# MOD-Y_cold_V03.net
KiCad netlist of a schematic drawn in EAGLE
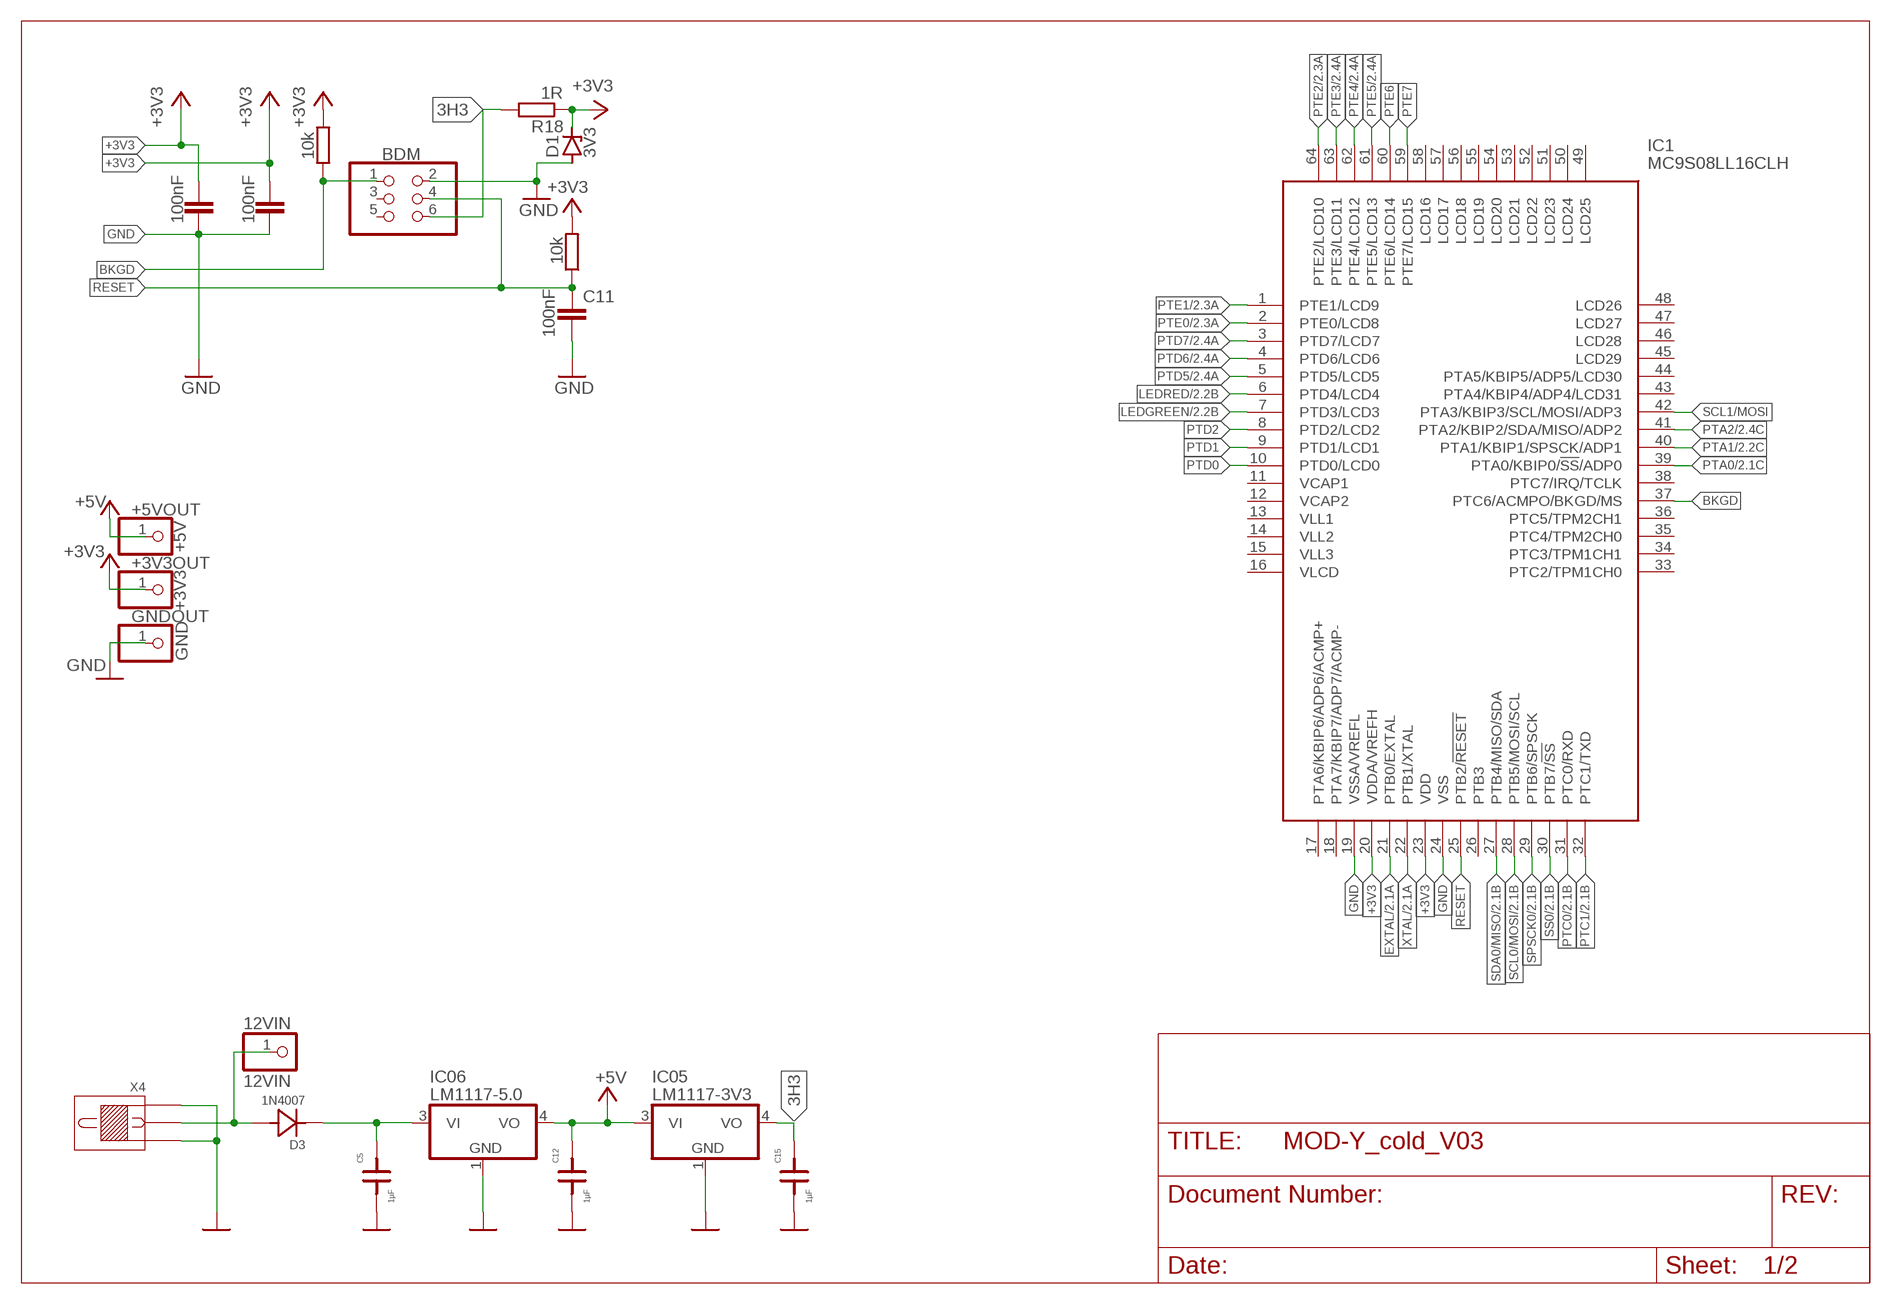
[diagram p0: schematic, sheet 1]
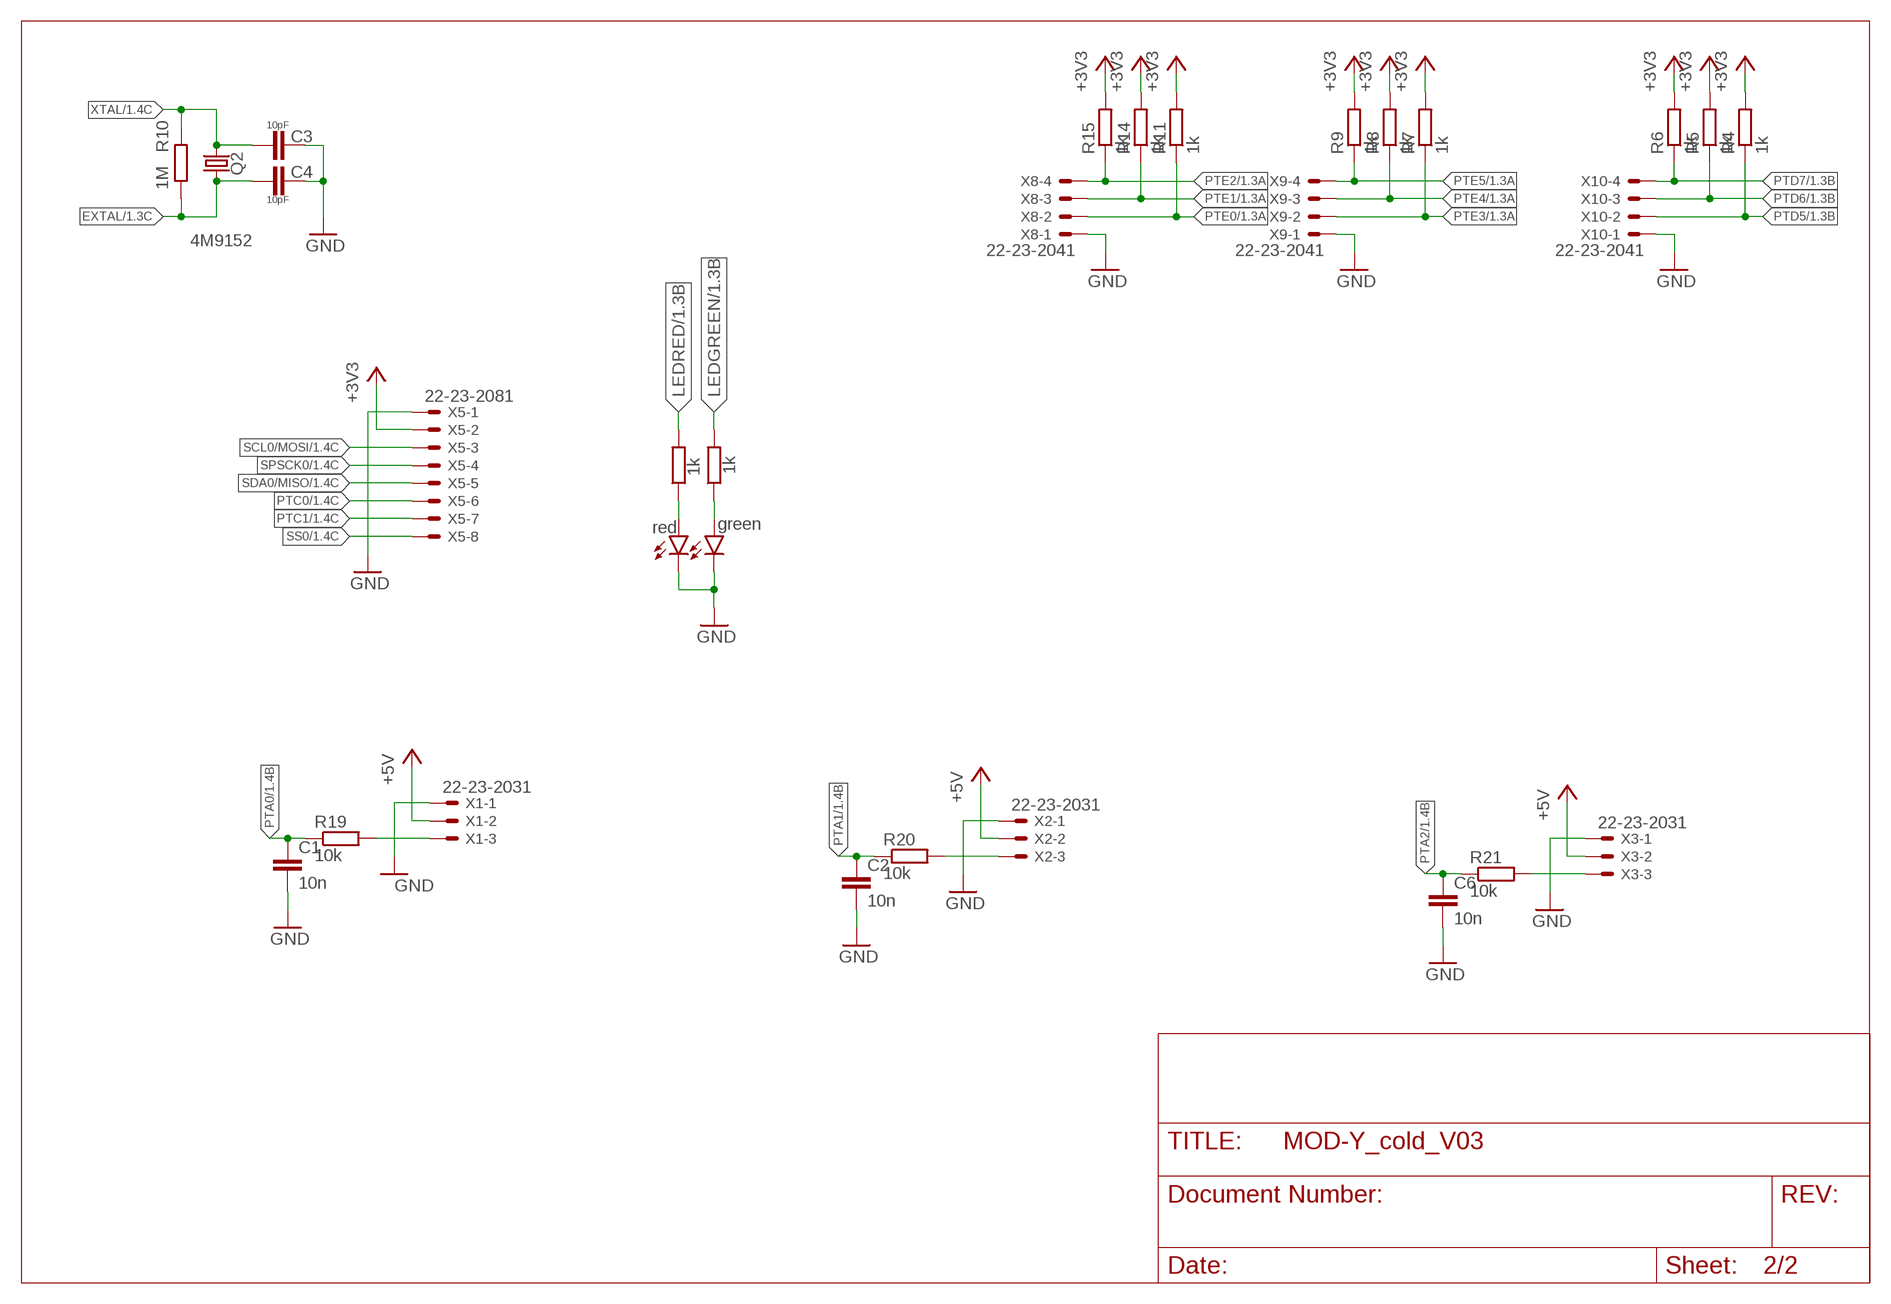
[diagram p1: schematic, sheet 2]

(export (version "E")
  (design (tool "Eeschema 10.0.6"))
  (components
    (comp (ref "C1")
      (value "10n")
      (footprint "eagle-import:C0805")
      (libsource (lib "eagle-import") (part "C-EUC0805"))
    )
    (comp (ref "C2")
      (value "10n")
      (footprint "eagle-import:C0805")
      (libsource (lib "eagle-import") (part "C-EUC0805"))
    )
    (comp (ref "C3")
      (value "10pF")
      (footprint "eagle-import:C0805")
      (libsource (lib "eagle-import") (part "C-EUC0805"))
    )
    (comp (ref "C4")
      (value "10pF")
      (footprint "eagle-import:C0805")
      (libsource (lib "eagle-import") (part "C-EUC0805"))
    )
    (comp (ref "C6")
      (value "10n")
      (footprint "eagle-import:C0805")
      (libsource (lib "eagle-import") (part "C-EUC0805"))
    )
    (comp (ref "LED1")
      (value "green")
      (footprint "eagle-import:CHIP-LED0805")
      (libsource (lib "eagle-import") (part "LEDCHIP-LED0805"))
    )
    (comp (ref "LED2")
      (value "red")
      (footprint "eagle-import:CHIP-LED0805")
      (libsource (lib "eagle-import") (part "LEDCHIP-LED0805"))
    )
    (comp (ref "Q2")
      (value "4M9152")
      (footprint "eagle-import:HC49UP")
      (libsource (lib "eagle-import") (part "CRYSTALHC49UP"))
    )
    (comp (ref "R4")
      (value "1k")
      (footprint "eagle-import:R0805")
      (libsource (lib "eagle-import") (part "R-EU_R0805"))
    )
    (comp (ref "R5")
      (value "1k")
      (footprint "eagle-import:R0805")
      (libsource (lib "eagle-import") (part "R-EU_R0805"))
    )
    (comp (ref "R6")
      (value "1k")
      (footprint "eagle-import:R0805")
      (libsource (lib "eagle-import") (part "R-EU_R0805"))
    )
    (comp (ref "R7")
      (value "1k")
      (footprint "eagle-import:R0805")
      (libsource (lib "eagle-import") (part "R-EU_R0805"))
    )
    (comp (ref "R8")
      (value "1k")
      (footprint "eagle-import:R0805")
      (libsource (lib "eagle-import") (part "R-EU_R0805"))
    )
    (comp (ref "R9")
      (value "1k")
      (footprint "eagle-import:R0805")
      (libsource (lib "eagle-import") (part "R-EU_R0805"))
    )
    (comp (ref "R10")
      (value "1M")
      (footprint "eagle-import:R0805")
      (libsource (lib "eagle-import") (part "R-EU_R0805"))
    )
    (comp (ref "R11")
      (value "1k")
      (footprint "eagle-import:R0805")
      (libsource (lib "eagle-import") (part "R-EU_R0805"))
    )
    (comp (ref "R12")
      (value "1k")
      (footprint "eagle-import:R0805")
      (libsource (lib "eagle-import") (part "R-EU_R0805"))
    )
    (comp (ref "R13")
      (value "1k")
      (footprint "eagle-import:R0805")
      (libsource (lib "eagle-import") (part "R-EU_R0805"))
    )
    (comp (ref "R14")
      (value "1k")
      (footprint "eagle-import:R0805")
      (libsource (lib "eagle-import") (part "R-EU_R0805"))
    )
    (comp (ref "R15")
      (value "1k")
      (footprint "eagle-import:R0805")
      (libsource (lib "eagle-import") (part "R-EU_R0805"))
    )
    (comp (ref "R19")
      (value "10k")
      (footprint "eagle-import:R0805")
      (libsource (lib "eagle-import") (part "R-EU_R0805"))
    )
    (comp (ref "R20")
      (value "10k")
      (footprint "eagle-import:R0805")
      (libsource (lib "eagle-import") (part "R-EU_R0805"))
    )
    (comp (ref "R21")
      (value "10k")
      (footprint "eagle-import:R0805")
      (libsource (lib "eagle-import") (part "R-EU_R0805"))
    )
    (comp (ref "X1")
      (value "22-23-2031")
      (footprint "eagle-import:22-23-2031")
      (fields (field (name "MF") "MOLEX"))
      (libsource (lib "eagle-import") (part "22-23-2031"))
    )
    (comp (ref "X2")
      (value "22-23-2031")
      (footprint "eagle-import:22-23-2031")
      (fields (field (name "MF") "MOLEX"))
      (libsource (lib "eagle-import") (part "22-23-2031"))
    )
    (comp (ref "X3")
      (value "22-23-2031")
      (footprint "eagle-import:22-23-2031")
      (fields (field (name "MF") "MOLEX"))
      (libsource (lib "eagle-import") (part "22-23-2031"))
    )
    (comp (ref "X5")
      (value "22-23-2081")
      (footprint "eagle-import:22-23-2081")
      (fields (field (name "MF") "MOLEX"))
      (libsource (lib "eagle-import") (part "22-23-2081"))
    )
    (comp (ref "X8")
      (value "22-23-2041")
      (footprint "eagle-import:22-23-2041")
      (fields (field (name "MF") "MOLEX"))
      (libsource (lib "eagle-import") (part "22-23-2041"))
    )
    (comp (ref "X9")
      (value "22-23-2041")
      (footprint "eagle-import:22-23-2041")
      (fields (field (name "MF") "MOLEX"))
      (libsource (lib "eagle-import") (part "22-23-2041"))
    )
    (comp (ref "X10")
      (value "22-23-2041")
      (footprint "eagle-import:22-23-2041")
      (fields (field (name "MF") "MOLEX"))
      (libsource (lib "eagle-import") (part "22-23-2041"))
    )
    (comp (ref "+3V3OUT")
      (value "+3V3")
      (footprint "eagle-import:1X01")
      (libsource (lib "eagle-import") (part "PINHD-1X1"))
    )
    (comp (ref "+5VOUT")
      (value "+5V")
      (footprint "eagle-import:1X01")
      (libsource (lib "eagle-import") (part "PINHD-1X1"))
    )
    (comp (ref "12VIN")
      (value "12VIN")
      (footprint "eagle-import:1X01")
      (libsource (lib "eagle-import") (part "PINHD-1X1"))
    )
    (comp (ref "BDM")
      (value "PINHD-2X3")
      (footprint "eagle-import:2X03")
      (libsource (lib "eagle-import") (part "PINHD-2X3"))
    )
    (comp (ref "C5")
      (value "1µF")
      (footprint "eagle-import:0805F")
      (libsource (lib "eagle-import") (part "C1"))
    )
    (comp (ref "C9")
      (value "100nF")
      (footprint "eagle-import:C0805")
      (libsource (lib "eagle-import") (part "C-EUC0805"))
    )
    (comp (ref "C10")
      (value "100nF")
      (footprint "eagle-import:C0805")
      (libsource (lib "eagle-import") (part "C-EUC0805"))
    )
    (comp (ref "C11")
      (value "100nF")
      (footprint "eagle-import:C0805")
      (libsource (lib "eagle-import") (part "C-EUC0805"))
    )
    (comp (ref "C12")
      (value "1µF")
      (footprint "eagle-import:0805F")
      (libsource (lib "eagle-import") (part "C1"))
    )
    (comp (ref "C15")
      (value "1µF")
      (footprint "eagle-import:0805F")
      (libsource (lib "eagle-import") (part "C1"))
    )
    (comp (ref "D1")
      (value "3V3")
      (footprint "eagle-import:SOD80C")
      (libsource (lib "eagle-import") (part "ZENER-DIODESOD80C"))
    )
    (comp (ref "D3")
      (value "1N4007")
      (footprint "eagle-import:MELF_B")
      (libsource (lib "eagle-import") (part "DHCMELF"))
    )
    (comp (ref "GNDOUT")
      (value "GND")
      (footprint "eagle-import:1X01")
      (libsource (lib "eagle-import") (part "PINHD-1X1"))
    )
    (comp (ref "IC1")
      (value "MC9S08LL16CLH")
      (footprint "eagle-import:QFP50P1200X1200X160-64N")
      (fields (field (name "MOUSER_PART_NUMBER") "841-MC9S08LL16CLH"))
      (libsource (lib "eagle-import") (part "MC9S08LL16CLH"))
    )
    (comp (ref "IC05")
      (value "LM1117-3V3")
      (footprint "eagle-import:DPAK")
      (libsource (lib "eagle-import") (part "LM1117DT"))
    )
    (comp (ref "IC06")
      (value "LM1117-5.0")
      (footprint "eagle-import:DPAK")
      (libsource (lib "eagle-import") (part "LM1117DT"))
    )
    (comp (ref "R16")
      (value "10k")
      (footprint "eagle-import:R0805")
      (libsource (lib "eagle-import") (part "R-EU_R0805"))
    )
    (comp (ref "R17")
      (value "10k")
      (footprint "eagle-import:R0805")
      (libsource (lib "eagle-import") (part "R-EU_R0805"))
    )
    (comp (ref "R18")
      (value "1R")
      (footprint "eagle-import:R0805")
      (libsource (lib "eagle-import") (part "R-EU_R0805"))
    )
    (comp (ref "X4")
      (value "SPP")
      (footprint "eagle-import:SPP")
      (libsource (lib "eagle-import") (part "SPP"))
    )
  )
  (nets
    (net (code "1") (name "+3V3") (class "Default")
      (node (ref "+3V3OUT") (pin "1") (pinfunction "1_1") (pintype "passive"))
      (node (ref "C10") (pin "1") (pinfunction "1_1") (pintype "passive"))
      (node (ref "C9") (pin "1") (pinfunction "1_1") (pintype "passive"))
      (node (ref "D1") (pin "C") (pinfunction "C_C") (pintype "passive"))
      (node (ref "IC1") (pin "20") (pinfunction "VDDA/VREFH_20") (pintype "bidirectional"))
      (node (ref "IC1") (pin "23") (pinfunction "VDD_23") (pintype "bidirectional"))
      (node (ref "R11") (pin "2") (pinfunction "2_2") (pintype "passive"))
      (node (ref "R14") (pin "2") (pinfunction "2_2") (pintype "passive"))
      (node (ref "R15") (pin "2") (pinfunction "2_2") (pintype "passive"))
      (node (ref "R16") (pin "2") (pinfunction "2_2") (pintype "passive"))
      (node (ref "R17") (pin "2") (pinfunction "2_2") (pintype "passive"))
      (node (ref "R18") (pin "1") (pinfunction "1_1") (pintype "passive"))
      (node (ref "R4") (pin "2") (pinfunction "2_2") (pintype "passive"))
      (node (ref "R5") (pin "2") (pinfunction "2_2") (pintype "passive"))
      (node (ref "R6") (pin "2") (pinfunction "2_2") (pintype "passive"))
      (node (ref "R7") (pin "2") (pinfunction "2_2") (pintype "passive"))
      (node (ref "R8") (pin "2") (pinfunction "2_2") (pintype "passive"))
      (node (ref "R9") (pin "2") (pinfunction "2_2") (pintype "passive"))
      (node (ref "X5") (pin "2") (pinfunction "S_2") (pintype "passive"))
    )
    (net (code "2") (name "+5V") (class "Default")
      (node (ref "+5VOUT") (pin "1") (pinfunction "1_1") (pintype "passive"))
      (node (ref "C12") (pin "2") (pinfunction "2_2") (pintype "bidirectional"))
      (node (ref "IC05") (pin "3") (pinfunction "VI_3") (pintype "input"))
      (node (ref "IC06") (pin "4") (pinfunction "VO_4") (pintype "output"))
      (node (ref "X1") (pin "2") (pinfunction "S_2") (pintype "passive"))
      (node (ref "X2") (pin "2") (pinfunction "S_2") (pintype "passive"))
      (node (ref "X3") (pin "2") (pinfunction "S_2") (pintype "passive"))
    )
    (net (code "3") (name "3H3") (class "Default")
      (node (ref "BDM") (pin "6") (pinfunction "6_6") (pintype "passive"))
      (node (ref "C15") (pin "2") (pinfunction "2_2") (pintype "bidirectional"))
      (node (ref "IC05") (pin "4") (pinfunction "VO_4") (pintype "output"))
      (node (ref "R18") (pin "2") (pinfunction "2_2") (pintype "passive"))
    )
    (net (code "4") (name "BKGD") (class "Default")
      (node (ref "BDM") (pin "1") (pinfunction "1_1") (pintype "passive"))
      (node (ref "IC1") (pin "37") (pinfunction "PTC6/ACMPO/BKGD/MS_37") (pintype "bidirectional"))
      (node (ref "R16") (pin "1") (pinfunction "1_1") (pintype "passive"))
    )
    (net (code "5") (name "EXTAL") (class "Default")
      (node (ref "C4") (pin "1") (pinfunction "1_1") (pintype "passive"))
      (node (ref "IC1") (pin "21") (pinfunction "PTB0/EXTAL_21") (pintype "bidirectional"))
      (node (ref "Q2") (pin "1") (pinfunction "1_1") (pintype "passive"))
      (node (ref "R10") (pin "1") (pinfunction "1_1") (pintype "passive"))
    )
    (net (code "6") (name "GND") (class "Default")
      (node (ref "BDM") (pin "2") (pinfunction "2_2") (pintype "passive"))
      (node (ref "C1") (pin "2") (pinfunction "2_2") (pintype "passive"))
      (node (ref "C10") (pin "2") (pinfunction "2_2") (pintype "passive"))
      (node (ref "C11") (pin "2") (pinfunction "2_2") (pintype "passive"))
      (node (ref "C12") (pin "1") (pinfunction "1_1") (pintype "bidirectional"))
      (node (ref "C15") (pin "1") (pinfunction "1_1") (pintype "bidirectional"))
      (node (ref "C2") (pin "2") (pinfunction "2_2") (pintype "passive"))
      (node (ref "C3") (pin "2") (pinfunction "2_2") (pintype "passive"))
      (node (ref "C4") (pin "2") (pinfunction "2_2") (pintype "passive"))
      (node (ref "C5") (pin "1") (pinfunction "1_1") (pintype "bidirectional"))
      (node (ref "C6") (pin "2") (pinfunction "2_2") (pintype "passive"))
      (node (ref "C9") (pin "2") (pinfunction "2_2") (pintype "passive"))
      (node (ref "D1") (pin "A") (pinfunction "A_A") (pintype "passive"))
      (node (ref "GNDOUT") (pin "1") (pinfunction "1_1") (pintype "passive"))
      (node (ref "IC05") (pin "1") (pinfunction "GND_1") (pintype "input"))
      (node (ref "IC06") (pin "1") (pinfunction "GND_1") (pintype "input"))
      (node (ref "IC1") (pin "19") (pinfunction "VSSA/VREFL_19") (pintype "bidirectional"))
      (node (ref "IC1") (pin "24") (pinfunction "VSS_24") (pintype "bidirectional"))
      (node (ref "LED1") (pin "C") (pinfunction "C_C") (pintype "passive"))
      (node (ref "LED2") (pin "C") (pinfunction "C_C") (pintype "passive"))
      (node (ref "X1") (pin "1") (pinfunction "S_1") (pintype "passive"))
      (node (ref "X10") (pin "1") (pinfunction "S_1") (pintype "passive"))
      (node (ref "X2") (pin "1") (pinfunction "S_1") (pintype "passive"))
      (node (ref "X3") (pin "1") (pinfunction "S_1") (pintype "passive"))
      (node (ref "X4") (pin "1") (pinfunction "1_1") (pintype "bidirectional"))
      (node (ref "X4") (pin "3") (pinfunction "3_3") (pintype "bidirectional"))
      (node (ref "X5") (pin "1") (pinfunction "S_1") (pintype "passive"))
      (node (ref "X8") (pin "1") (pinfunction "S_1") (pintype "passive"))
      (node (ref "X9") (pin "1") (pinfunction "S_1") (pintype "passive"))
    )
    (net (code "7") (name "LEDGREEN") (class "Default")
      (node (ref "IC1") (pin "7") (pinfunction "PTD3/LCD3_7") (pintype "bidirectional"))
      (node (ref "R13") (pin "2") (pinfunction "2_2") (pintype "passive"))
    )
    (net (code "8") (name "LEDRED") (class "Default")
      (node (ref "IC1") (pin "6") (pinfunction "PTD4/LCD4_6") (pintype "bidirectional"))
      (node (ref "R12") (pin "2") (pinfunction "2_2") (pintype "passive"))
    )
    (net (code "9") (name "Net-(12VIN-Pad1)") (class "Default")
      (node (ref "12VIN") (pin "1") (pinfunction "1_1") (pintype "passive"))
      (node (ref "D3") (pin "A") (pinfunction "A_A") (pintype "bidirectional"))
      (node (ref "X4") (pin "2") (pinfunction "2_2") (pintype "bidirectional"))
    )
    (net (code "10") (name "Net-(IC06-VI)") (class "Default")
      (node (ref "C5") (pin "2") (pinfunction "2_2") (pintype "bidirectional"))
      (node (ref "D3") (pin "K") (pinfunction "K_K") (pintype "bidirectional"))
      (node (ref "IC06") (pin "3") (pinfunction "VI_3") (pintype "input"))
    )
    (net (code "11") (name "Net-(LED1-PadA)") (class "Default")
      (node (ref "LED1") (pin "A") (pinfunction "A_A") (pintype "passive"))
      (node (ref "R13") (pin "1") (pinfunction "1_1") (pintype "passive"))
    )
    (net (code "12") (name "Net-(LED2-PadA)") (class "Default")
      (node (ref "LED2") (pin "A") (pinfunction "A_A") (pintype "passive"))
      (node (ref "R12") (pin "1") (pinfunction "1_1") (pintype "passive"))
    )
    (net (code "13") (name "Net-(X1C-S)") (class "Default")
      (node (ref "R19") (pin "2") (pinfunction "2_2") (pintype "passive"))
      (node (ref "X1") (pin "3") (pinfunction "S_3") (pintype "passive"))
    )
    (net (code "14") (name "Net-(X2C-S)") (class "Default")
      (node (ref "R20") (pin "2") (pinfunction "2_2") (pintype "passive"))
      (node (ref "X2") (pin "3") (pinfunction "S_3") (pintype "passive"))
    )
    (net (code "15") (name "Net-(X3C-S)") (class "Default")
      (node (ref "R21") (pin "2") (pinfunction "2_2") (pintype "passive"))
      (node (ref "X3") (pin "3") (pinfunction "S_3") (pintype "passive"))
    )
    (net (code "16") (name "PTA0") (class "Default")
      (node (ref "C1") (pin "1") (pinfunction "1_1") (pintype "passive"))
      (node (ref "IC1") (pin "39") (pinfunction "PTA0/KBIP0/~{SS}/ADP0_39") (pintype "bidirectional"))
      (node (ref "R19") (pin "1") (pinfunction "1_1") (pintype "passive"))
    )
    (net (code "17") (name "PTA1") (class "Default")
      (node (ref "C2") (pin "1") (pinfunction "1_1") (pintype "passive"))
      (node (ref "IC1") (pin "40") (pinfunction "PTA1/KBIP1/SPSCK/ADP1_40") (pintype "bidirectional"))
      (node (ref "R20") (pin "1") (pinfunction "1_1") (pintype "passive"))
    )
    (net (code "18") (name "PTA2") (class "Default")
      (node (ref "C6") (pin "1") (pinfunction "1_1") (pintype "passive"))
      (node (ref "IC1") (pin "41") (pinfunction "PTA2/KBIP2/SDA/MISO/ADP2_41") (pintype "bidirectional"))
      (node (ref "R21") (pin "1") (pinfunction "1_1") (pintype "passive"))
    )
    (net (code "19") (name "PTC0") (class "Default")
      (node (ref "IC1") (pin "31") (pinfunction "PTC0/RXD_31") (pintype "bidirectional"))
      (node (ref "X5") (pin "6") (pinfunction "S_6") (pintype "passive"))
    )
    (net (code "20") (name "PTC1") (class "Default")
      (node (ref "IC1") (pin "32") (pinfunction "PTC1/TXD_32") (pintype "bidirectional"))
      (node (ref "X5") (pin "7") (pinfunction "S_7") (pintype "passive"))
    )
    (net (code "21") (name "PTD0") (class "Default")
      (node (ref "IC1") (pin "10") (pinfunction "PTD0/LCD0_10") (pintype "bidirectional"))
    )
    (net (code "22") (name "PTD1") (class "Default")
      (node (ref "IC1") (pin "9") (pinfunction "PTD1/LCD1_9") (pintype "bidirectional"))
    )
    (net (code "23") (name "PTD2") (class "Default")
      (node (ref "IC1") (pin "8") (pinfunction "PTD2/LCD2_8") (pintype "bidirectional"))
    )
    (net (code "24") (name "PTD5") (class "Default")
      (node (ref "IC1") (pin "5") (pinfunction "PTD5/LCD5_5") (pintype "bidirectional"))
      (node (ref "R4") (pin "1") (pinfunction "1_1") (pintype "passive"))
      (node (ref "X10") (pin "2") (pinfunction "S_2") (pintype "passive"))
    )
    (net (code "25") (name "PTD6") (class "Default")
      (node (ref "IC1") (pin "4") (pinfunction "PTD6/LCD6_4") (pintype "bidirectional"))
      (node (ref "R5") (pin "1") (pinfunction "1_1") (pintype "passive"))
      (node (ref "X10") (pin "3") (pinfunction "S_3") (pintype "passive"))
    )
    (net (code "26") (name "PTD7") (class "Default")
      (node (ref "IC1") (pin "3") (pinfunction "PTD7/LCD7_3") (pintype "bidirectional"))
      (node (ref "R6") (pin "1") (pinfunction "1_1") (pintype "passive"))
      (node (ref "X10") (pin "4") (pinfunction "S_4") (pintype "passive"))
    )
    (net (code "27") (name "PTE0") (class "Default")
      (node (ref "IC1") (pin "2") (pinfunction "PTE0/LCD8_2") (pintype "bidirectional"))
      (node (ref "R11") (pin "1") (pinfunction "1_1") (pintype "passive"))
      (node (ref "X8") (pin "2") (pinfunction "S_2") (pintype "passive"))
    )
    (net (code "28") (name "PTE1") (class "Default")
      (node (ref "IC1") (pin "1") (pinfunction "PTE1/LCD9_1") (pintype "bidirectional"))
      (node (ref "R14") (pin "1") (pinfunction "1_1") (pintype "passive"))
      (node (ref "X8") (pin "3") (pinfunction "S_3") (pintype "passive"))
    )
    (net (code "29") (name "PTE2") (class "Default")
      (node (ref "IC1") (pin "64") (pinfunction "PTE2/LCD10_64") (pintype "bidirectional"))
      (node (ref "R15") (pin "1") (pinfunction "1_1") (pintype "passive"))
      (node (ref "X8") (pin "4") (pinfunction "S_4") (pintype "passive"))
    )
    (net (code "30") (name "PTE3") (class "Default")
      (node (ref "IC1") (pin "63") (pinfunction "PTE3/LCD11_63") (pintype "bidirectional"))
      (node (ref "R7") (pin "1") (pinfunction "1_1") (pintype "passive"))
      (node (ref "X9") (pin "2") (pinfunction "S_2") (pintype "passive"))
    )
    (net (code "31") (name "PTE4") (class "Default")
      (node (ref "IC1") (pin "62") (pinfunction "PTE4/LCD12_62") (pintype "bidirectional"))
      (node (ref "R8") (pin "1") (pinfunction "1_1") (pintype "passive"))
      (node (ref "X9") (pin "3") (pinfunction "S_3") (pintype "passive"))
    )
    (net (code "32") (name "PTE5") (class "Default")
      (node (ref "IC1") (pin "61") (pinfunction "PTE5/LCD13_61") (pintype "bidirectional"))
      (node (ref "R9") (pin "1") (pinfunction "1_1") (pintype "passive"))
      (node (ref "X9") (pin "4") (pinfunction "S_4") (pintype "passive"))
    )
    (net (code "33") (name "PTE6") (class "Default")
      (node (ref "IC1") (pin "60") (pinfunction "PTE6/LCD14_60") (pintype "bidirectional"))
    )
    (net (code "34") (name "PTE7") (class "Default")
      (node (ref "IC1") (pin "59") (pinfunction "PTE7/LCD15_59") (pintype "bidirectional"))
    )
    (net (code "35") (name "RESET") (class "Default")
      (node (ref "BDM") (pin "4") (pinfunction "4_4") (pintype "passive"))
      (node (ref "C11") (pin "1") (pinfunction "1_1") (pintype "passive"))
      (node (ref "IC1") (pin "25") (pinfunction "PTB2/~{RESET}_25") (pintype "bidirectional"))
      (node (ref "R17") (pin "1") (pinfunction "1_1") (pintype "passive"))
    )
    (net (code "36") (name "SCL0{slash}MOSI") (class "Default")
      (node (ref "IC1") (pin "28") (pinfunction "PTB5/MOSI/SCL_28") (pintype "bidirectional"))
      (node (ref "X5") (pin "3") (pinfunction "S_3") (pintype "passive"))
    )
    (net (code "37") (name "SCL1{slash}MOSI") (class "Default")
      (node (ref "IC1") (pin "42") (pinfunction "PTA3/KBIP3/SCL/MOSI/ADP3_42") (pintype "bidirectional"))
    )
    (net (code "38") (name "SDA0{slash}MISO") (class "Default")
      (node (ref "IC1") (pin "27") (pinfunction "PTB4/MISO/SDA_27") (pintype "bidirectional"))
      (node (ref "X5") (pin "5") (pinfunction "S_5") (pintype "passive"))
    )
    (net (code "39") (name "SPSCK0") (class "Default")
      (node (ref "IC1") (pin "29") (pinfunction "PTB6/SPSCK_29") (pintype "bidirectional"))
      (node (ref "X5") (pin "4") (pinfunction "S_4") (pintype "passive"))
    )
    (net (code "40") (name "SS0") (class "Default")
      (node (ref "IC1") (pin "30") (pinfunction "PTB7/~{SS}_30") (pintype "bidirectional"))
      (node (ref "X5") (pin "8") (pinfunction "S_8") (pintype "passive"))
    )
    (net (code "41") (name "XTAL") (class "Default")
      (node (ref "C3") (pin "1") (pinfunction "1_1") (pintype "passive"))
      (node (ref "IC1") (pin "22") (pinfunction "PTB1/XTAL_22") (pintype "bidirectional"))
      (node (ref "Q2") (pin "2") (pinfunction "2_2") (pintype "passive"))
      (node (ref "R10") (pin "2") (pinfunction "2_2") (pintype "passive"))
    )
    (net (code "42") (name "unconnected-(BDM-Pad3)") (class "Default")
      (node (ref "BDM") (pin "3") (pinfunction "3_3") (pintype "passive"))
    )
    (net (code "43") (name "unconnected-(BDM-Pad5)") (class "Default")
      (node (ref "BDM") (pin "5") (pinfunction "5_5") (pintype "passive"))
    )
    (net (code "44") (name "unconnected-(IC1-LCD16-Pad58)") (class "Default")
      (node (ref "IC1") (pin "58") (pinfunction "LCD16_58") (pintype "bidirectional"))
    )
    (net (code "45") (name "unconnected-(IC1-LCD17-Pad57)") (class "Default")
      (node (ref "IC1") (pin "57") (pinfunction "LCD17_57") (pintype "bidirectional"))
    )
    (net (code "46") (name "unconnected-(IC1-LCD18-Pad56)") (class "Default")
      (node (ref "IC1") (pin "56") (pinfunction "LCD18_56") (pintype "bidirectional"))
    )
    (net (code "47") (name "unconnected-(IC1-LCD19-Pad55)") (class "Default")
      (node (ref "IC1") (pin "55") (pinfunction "LCD19_55") (pintype "bidirectional"))
    )
    (net (code "48") (name "unconnected-(IC1-LCD20-Pad54)") (class "Default")
      (node (ref "IC1") (pin "54") (pinfunction "LCD20_54") (pintype "bidirectional"))
    )
    (net (code "49") (name "unconnected-(IC1-LCD21-Pad53)") (class "Default")
      (node (ref "IC1") (pin "53") (pinfunction "LCD21_53") (pintype "bidirectional"))
    )
    (net (code "50") (name "unconnected-(IC1-LCD22-Pad52)") (class "Default")
      (node (ref "IC1") (pin "52") (pinfunction "LCD22_52") (pintype "bidirectional"))
    )
    (net (code "51") (name "unconnected-(IC1-LCD23-Pad51)") (class "Default")
      (node (ref "IC1") (pin "51") (pinfunction "LCD23_51") (pintype "bidirectional"))
    )
    (net (code "52") (name "unconnected-(IC1-LCD24-Pad50)") (class "Default")
      (node (ref "IC1") (pin "50") (pinfunction "LCD24_50") (pintype "bidirectional"))
    )
    (net (code "53") (name "unconnected-(IC1-LCD25-Pad49)") (class "Default")
      (node (ref "IC1") (pin "49") (pinfunction "LCD25_49") (pintype "bidirectional"))
    )
    (net (code "54") (name "unconnected-(IC1-LCD26-Pad48)") (class "Default")
      (node (ref "IC1") (pin "48") (pinfunction "LCD26_48") (pintype "bidirectional"))
    )
    (net (code "55") (name "unconnected-(IC1-LCD27-Pad47)") (class "Default")
      (node (ref "IC1") (pin "47") (pinfunction "LCD27_47") (pintype "bidirectional"))
    )
    (net (code "56") (name "unconnected-(IC1-LCD28-Pad46)") (class "Default")
      (node (ref "IC1") (pin "46") (pinfunction "LCD28_46") (pintype "bidirectional"))
    )
    (net (code "57") (name "unconnected-(IC1-LCD29-Pad45)") (class "Default")
      (node (ref "IC1") (pin "45") (pinfunction "LCD29_45") (pintype "bidirectional"))
    )
    (net (code "58") (name "unconnected-(IC1-PTA4{slash}KBIP4{slash}ADP4{slash}LCD31-Pad43)") (class "Default")
      (node (ref "IC1") (pin "43") (pinfunction "PTA4/KBIP4/ADP4/LCD31_43") (pintype "bidirectional"))
    )
    (net (code "59") (name "unconnected-(IC1-PTA5{slash}KBIP5{slash}ADP5{slash}LCD30-Pad44)") (class "Default")
      (node (ref "IC1") (pin "44") (pinfunction "PTA5/KBIP5/ADP5/LCD30_44") (pintype "bidirectional"))
    )
    (net (code "60") (name "unconnected-(IC1-PTA6{slash}KBIP6{slash}ADP6{slash}ACMP+-Pad17)") (class "Default")
      (node (ref "IC1") (pin "17") (pinfunction "PTA6/KBIP6/ADP6/ACMP+_17") (pintype "bidirectional"))
    )
    (net (code "61") (name "unconnected-(IC1-PTA7{slash}KBIP7{slash}ADP7{slash}ACMP--Pad18)") (class "Default")
      (node (ref "IC1") (pin "18") (pinfunction "PTA7/KBIP7/ADP7/ACMP-_18") (pintype "bidirectional"))
    )
    (net (code "62") (name "unconnected-(IC1-PTB3-Pad26)") (class "Default")
      (node (ref "IC1") (pin "26") (pinfunction "PTB3_26") (pintype "bidirectional"))
    )
    (net (code "63") (name "unconnected-(IC1-PTC2{slash}TPM1CH0-Pad33)") (class "Default")
      (node (ref "IC1") (pin "33") (pinfunction "PTC2/TPM1CH0_33") (pintype "bidirectional"))
    )
    (net (code "64") (name "unconnected-(IC1-PTC3{slash}TPM1CH1-Pad34)") (class "Default")
      (node (ref "IC1") (pin "34") (pinfunction "PTC3/TPM1CH1_34") (pintype "bidirectional"))
    )
    (net (code "65") (name "unconnected-(IC1-PTC4{slash}TPM2CH0-Pad35)") (class "Default")
      (node (ref "IC1") (pin "35") (pinfunction "PTC4/TPM2CH0_35") (pintype "bidirectional"))
    )
    (net (code "66") (name "unconnected-(IC1-PTC5{slash}TPM2CH1-Pad36)") (class "Default")
      (node (ref "IC1") (pin "36") (pinfunction "PTC5/TPM2CH1_36") (pintype "bidirectional"))
    )
    (net (code "67") (name "unconnected-(IC1-PTC7{slash}IRQ{slash}TCLK-Pad38)") (class "Default")
      (node (ref "IC1") (pin "38") (pinfunction "PTC7/IRQ/TCLK_38") (pintype "bidirectional"))
    )
    (net (code "68") (name "unconnected-(IC1-VCAP1-Pad11)") (class "Default")
      (node (ref "IC1") (pin "11") (pinfunction "VCAP1_11") (pintype "bidirectional"))
    )
    (net (code "69") (name "unconnected-(IC1-VCAP2-Pad12)") (class "Default")
      (node (ref "IC1") (pin "12") (pinfunction "VCAP2_12") (pintype "bidirectional"))
    )
    (net (code "70") (name "unconnected-(IC1-VLCD-Pad16)") (class "Default")
      (node (ref "IC1") (pin "16") (pinfunction "VLCD_16") (pintype "bidirectional"))
    )
    (net (code "71") (name "unconnected-(IC1-VLL1-Pad13)") (class "Default")
      (node (ref "IC1") (pin "13") (pinfunction "VLL1_13") (pintype "bidirectional"))
    )
    (net (code "72") (name "unconnected-(IC1-VLL2-Pad14)") (class "Default")
      (node (ref "IC1") (pin "14") (pinfunction "VLL2_14") (pintype "bidirectional"))
    )
    (net (code "73") (name "unconnected-(IC1-VLL3-Pad15)") (class "Default")
      (node (ref "IC1") (pin "15") (pinfunction "VLL3_15") (pintype "bidirectional"))
    )
  )
)
